# AirSensor.net
KiCad netlist of a schematic drawn in EAGLE
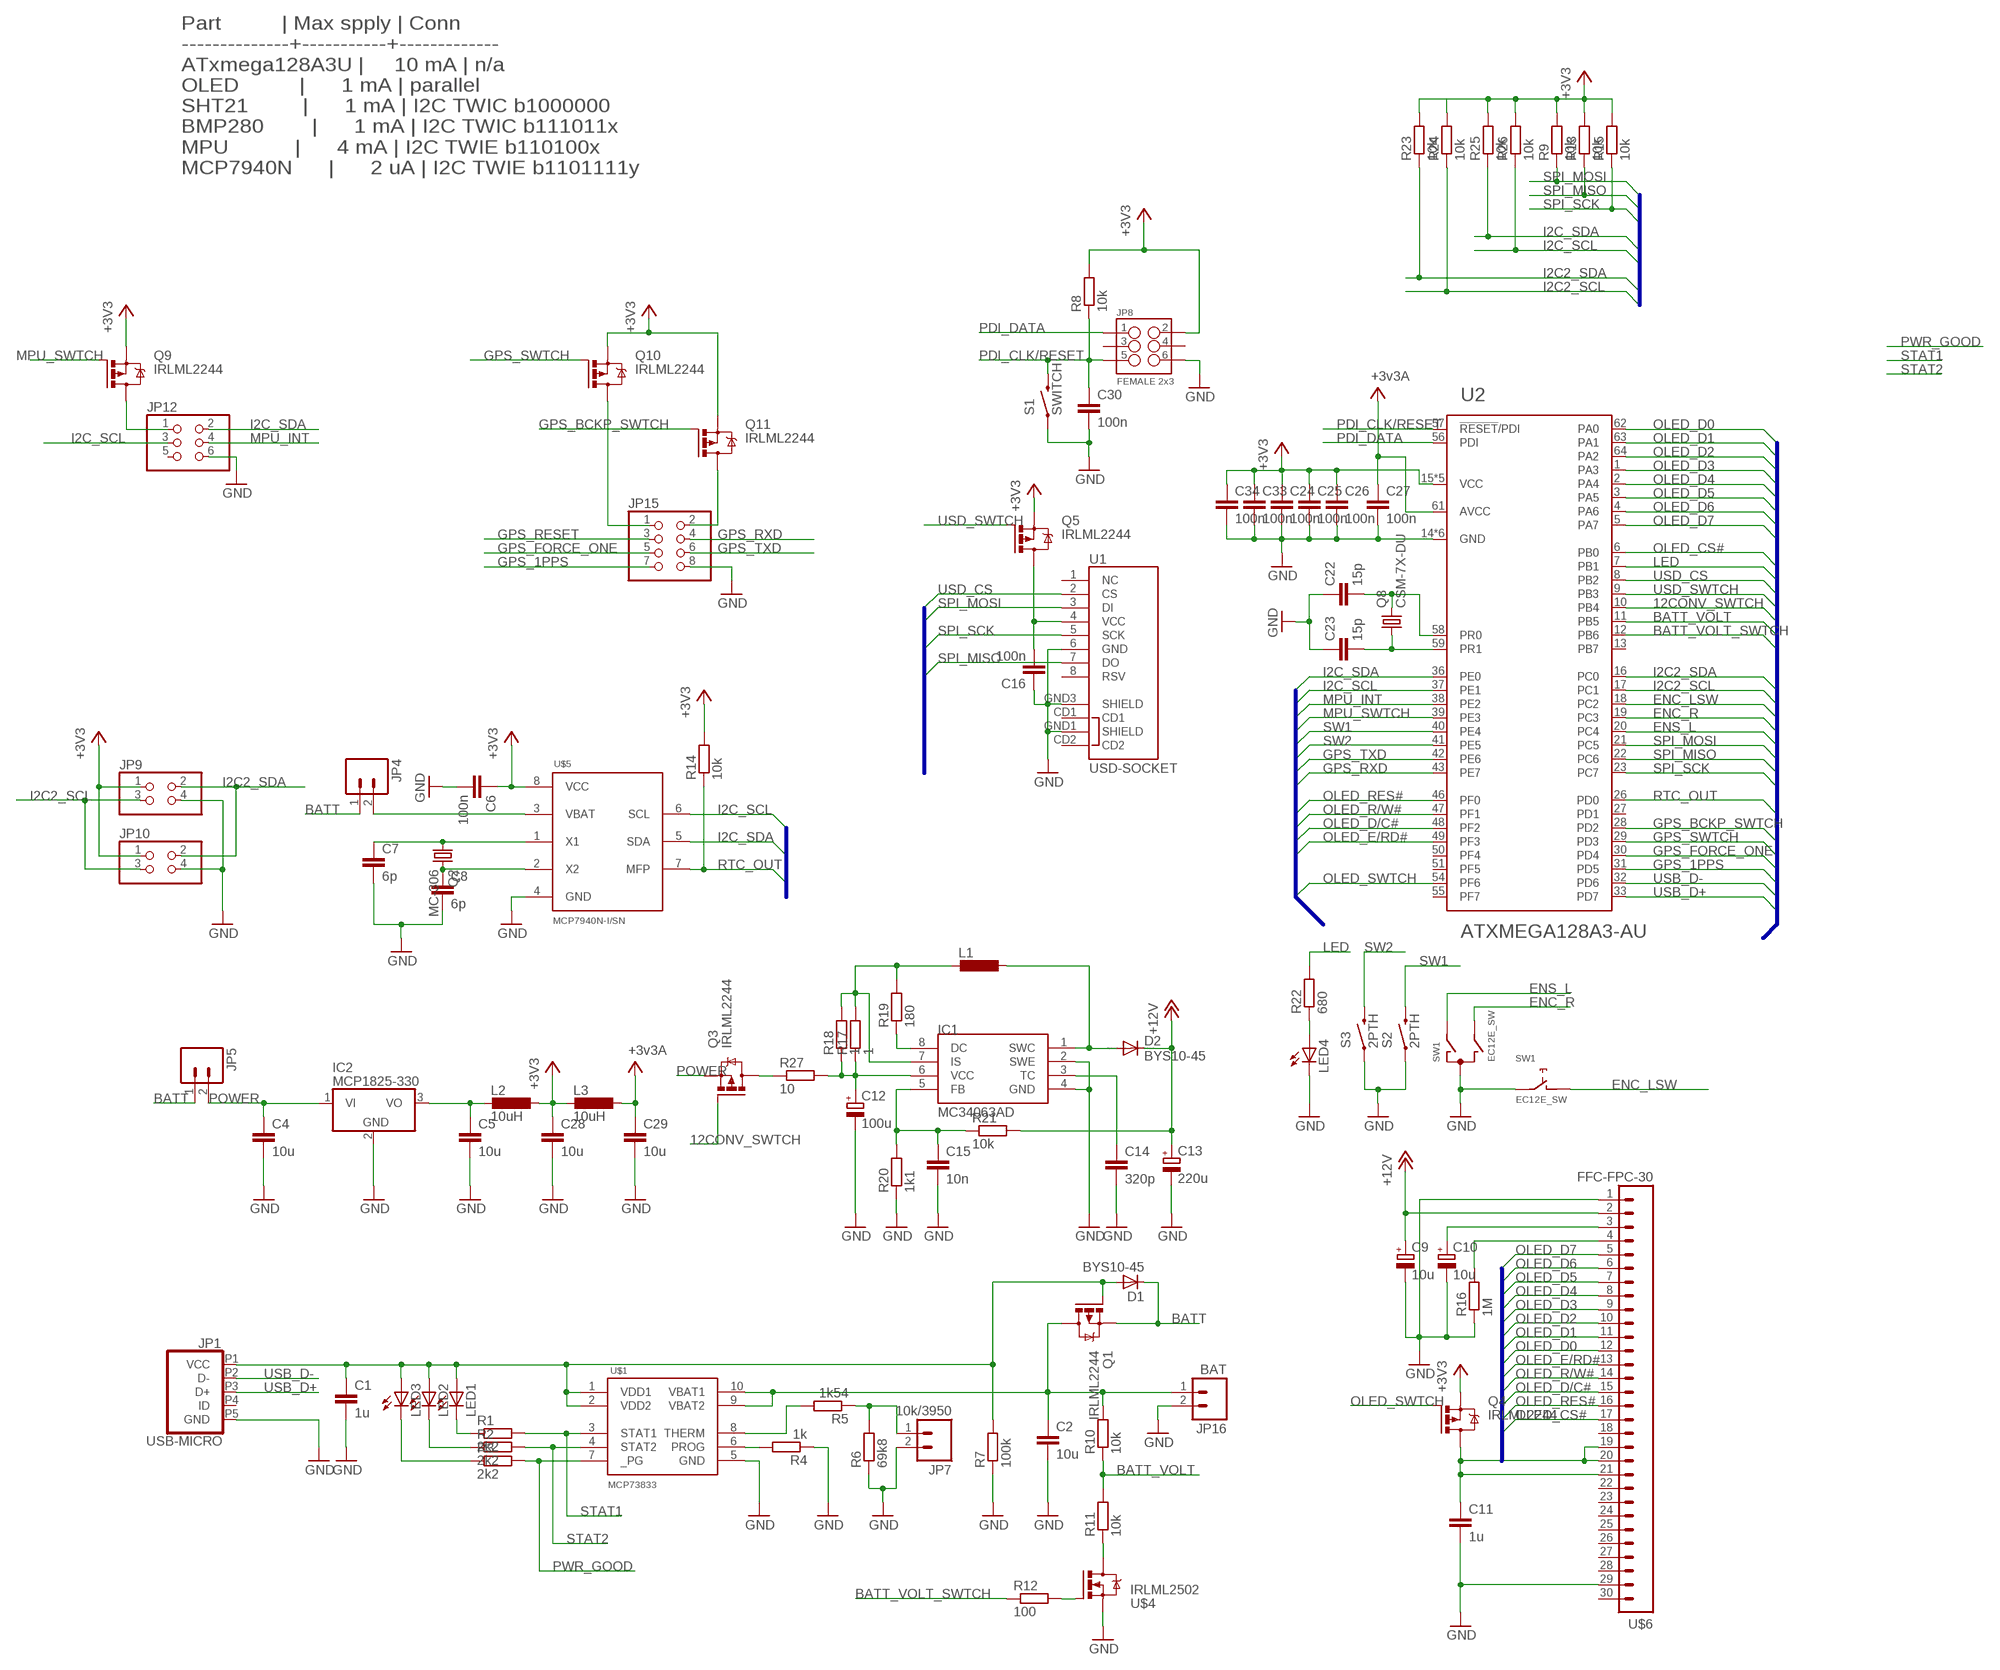
[diagram p0: schematic, sheet 1]

(export (version "E")
  (design (tool "Eeschema 10.0.6"))
  (components
    (comp (ref "C1")
      (value "1u")
      (footprint "eagle-import:C1206")
      (libsource (lib "eagle-import") (part "C-EUC1206"))
    )
    (comp (ref "C2")
      (value "10u")
      (footprint "eagle-import:C0805")
      (libsource (lib "eagle-import") (part "C-EUC0805"))
    )
    (comp (ref "C4")
      (value "10u")
      (footprint "eagle-import:C0805")
      (libsource (lib "eagle-import") (part "C-EUC0805"))
    )
    (comp (ref "C5")
      (value "10u")
      (footprint "eagle-import:C0805")
      (libsource (lib "eagle-import") (part "C-EUC0805"))
    )
    (comp (ref "C6")
      (value "100n")
      (footprint "eagle-import:C0805")
      (libsource (lib "eagle-import") (part "C-EUC0805"))
    )
    (comp (ref "C7")
      (value "6p")
      (footprint "eagle-import:C0805")
      (libsource (lib "eagle-import") (part "C-EUC0805"))
    )
    (comp (ref "C8")
      (value "6p")
      (footprint "eagle-import:C0805")
      (libsource (lib "eagle-import") (part "C-EUC0805"))
    )
    (comp (ref "C9")
      (value "10u")
      (footprint "eagle-import:UD-4X5,8_NICHICON")
      (libsource (lib "eagle-import") (part "CPOL-EUUD-4X5,8"))
    )
    (comp (ref "C10")
      (value "10u")
      (footprint "eagle-import:UD-4X5,8_NICHICON")
      (libsource (lib "eagle-import") (part "CPOL-EUUD-4X5,8"))
    )
    (comp (ref "C11")
      (value "1u")
      (footprint "eagle-import:C0805")
      (libsource (lib "eagle-import") (part "C-EUC0805"))
    )
    (comp (ref "C12")
      (value "100u")
      (footprint "eagle-import:SANYO-OSCON_SMD_C6")
      (libsource (lib "eagle-import") (part "CPOL-EUSANYO_SMD_C6"))
    )
    (comp (ref "C13")
      (value "220u")
      (footprint "eagle-import:SANYO-OSCON_SMD_C6")
      (libsource (lib "eagle-import") (part "CPOL-EUSANYO_SMD_C6"))
    )
    (comp (ref "C14")
      (value "320p")
      (footprint "eagle-import:C0805")
      (libsource (lib "eagle-import") (part "C-EUC0805"))
    )
    (comp (ref "C15")
      (value "10n")
      (footprint "eagle-import:C0805")
      (libsource (lib "eagle-import") (part "C-EUC0805"))
    )
    (comp (ref "C16")
      (value "100n")
      (footprint "eagle-import:C0805")
      (libsource (lib "eagle-import") (part "C-EUC0805"))
    )
    (comp (ref "C22")
      (value "15p")
      (footprint "eagle-import:C0805")
      (libsource (lib "eagle-import") (part "C-EUC0805"))
    )
    (comp (ref "C23")
      (value "15p")
      (footprint "eagle-import:C0805")
      (libsource (lib "eagle-import") (part "C-EUC0805"))
    )
    (comp (ref "C24")
      (value "100n")
      (footprint "eagle-import:C0805")
      (libsource (lib "eagle-import") (part "C-EUC0805"))
    )
    (comp (ref "C25")
      (value "100n")
      (footprint "eagle-import:C0805")
      (libsource (lib "eagle-import") (part "C-EUC0805"))
    )
    (comp (ref "C26")
      (value "100n")
      (footprint "eagle-import:C0805")
      (libsource (lib "eagle-import") (part "C-EUC0805"))
    )
    (comp (ref "C27")
      (value "100n")
      (footprint "eagle-import:C0805")
      (libsource (lib "eagle-import") (part "C-EUC0805"))
    )
    (comp (ref "C28")
      (value "10u")
      (footprint "eagle-import:C0805")
      (libsource (lib "eagle-import") (part "C-EUC0805"))
    )
    (comp (ref "C29")
      (value "10u")
      (footprint "eagle-import:C0805")
      (libsource (lib "eagle-import") (part "C-EUC0805"))
    )
    (comp (ref "C30")
      (value "100n")
      (footprint "eagle-import:C0805")
      (libsource (lib "eagle-import") (part "C-EUC0805"))
    )
    (comp (ref "C33")
      (value "100n")
      (footprint "eagle-import:C0805")
      (libsource (lib "eagle-import") (part "C-EUC0805"))
    )
    (comp (ref "C34")
      (value "100n")
      (footprint "eagle-import:C0805")
      (libsource (lib "eagle-import") (part "C-EUC0805"))
    )
    (comp (ref "D1")
      (value "BYS10-45")
      (footprint "eagle-import:SOD106A")
      (fields (field (name "MPN") "BYS10/45"))
      (libsource (lib "eagle-import") (part "BYS10"))
    )
    (comp (ref "D2")
      (value "BYS10-45")
      (footprint "eagle-import:SOD123")
      (libsource (lib "eagle-import") (part "MBR0520LT"))
    )
    (comp (ref "IC1")
      (value "MC34063AD")
      (footprint "eagle-import:SOIC8")
      (libsource (lib "eagle-import") (part "MC34063AD"))
    )
    (comp (ref "IC2")
      (value "MCP1825-330")
      (footprint "eagle-import:SOT223")
      (libsource (lib "eagle-import") (part "MCP1703DB"))
    )
    (comp (ref "JP1")
      (value "USB-MICRO")
      (footprint "eagle-import:HIROSE-ZX62-AB-5PA(11)")
      (libsource (lib "eagle-import") (part "USB-MICRO"))
    )
    (comp (ref "JP4")
      (value "M02PTH")
      (footprint "eagle-import:1X02")
      (libsource (lib "eagle-import") (part "M02PTH"))
    )
    (comp (ref "JP5")
      (value "M02PTH")
      (footprint "eagle-import:1X02")
      (libsource (lib "eagle-import") (part "M02PTH"))
    )
    (comp (ref "JP7")
      (value "10k/3950")
      (footprint "eagle-import:1X02")
      (libsource (lib "eagle-import") (part "M02PTH"))
    )
    (comp (ref "JP8")
      (value "FEMALE 2x3")
      (footprint "eagle-import:2X3")
      (libsource (lib "eagle-import") (part "M03X2FEMALE"))
    )
    (comp (ref "JP9")
      (value "PINHD-2X2/90-SOCKET")
      (footprint "eagle-import:2X02S_90")
      (libsource (lib "eagle-import") (part "PINHD-2X2/90-SOCKET"))
    )
    (comp (ref "JP10")
      (value "PINHD-2X2/90-SOCKET")
      (footprint "eagle-import:2X02S_90")
      (libsource (lib "eagle-import") (part "PINHD-2X2/90-SOCKET"))
    )
    (comp (ref "JP12")
      (value "PINHD-2X3/90-SOCKET")
      (footprint "eagle-import:2X03S_90")
      (libsource (lib "eagle-import") (part "PINHD-2X3/90-SOCKET"))
    )
    (comp (ref "JP15")
      (value "PINHD-2X4/90-SOCKET")
      (footprint "eagle-import:2X04S_90")
      (libsource (lib "eagle-import") (part "PINHD-2X4/90-SOCKET"))
    )
    (comp (ref "JP16")
      (value "BAT")
      (footprint "eagle-import:1X02")
      (libsource (lib "eagle-import") (part "M02PTH"))
    )
    (comp (ref "L1")
      (value "L-EUTFI0307")
      (footprint "eagle-import:TFI0307")
      (libsource (lib "eagle-import") (part "L-EUTFI0307"))
    )
    (comp (ref "L2")
      (value "10uH")
      (footprint "eagle-import:L3225P")
      (libsource (lib "eagle-import") (part "L-EUL3225P"))
    )
    (comp (ref "L3")
      (value "10uH")
      (footprint "eagle-import:L3225P")
      (libsource (lib "eagle-import") (part "L-EUL3225P"))
    )
    (comp (ref "LED1")
      (value "LEDCHIPLED_1206")
      (footprint "eagle-import:CHIPLED_1206")
      (libsource (lib "eagle-import") (part "LEDCHIPLED_1206"))
    )
    (comp (ref "LED2")
      (value "LEDCHIPLED_1206")
      (footprint "eagle-import:CHIPLED_1206")
      (libsource (lib "eagle-import") (part "LEDCHIPLED_1206"))
    )
    (comp (ref "LED3")
      (value "LEDCHIPLED_1206")
      (footprint "eagle-import:CHIPLED_1206")
      (libsource (lib "eagle-import") (part "LEDCHIPLED_1206"))
    )
    (comp (ref "LED4")
      (value "LEDSML1206")
      (footprint "eagle-import:SML1206")
      (libsource (lib "eagle-import") (part "LEDSML1206"))
    )
    (comp (ref "Q1")
      (value "IRLML2244")
      (footprint "eagle-import:MICRO3")
      (libsource (lib "eagle-import") (part "IRLML5203"))
    )
    (comp (ref "Q2")
      (value "MC-306")
      (footprint "eagle-import:MC-306")
      (fields (field (name "MPN") "MC-306 60.0KHZ  100PPM ,12.5PF"))
      (libsource (lib "eagle-import") (part "MC-306"))
    )
    (comp (ref "Q3")
      (value "IRLML2244")
      (footprint "eagle-import:MICRO3")
      (libsource (lib "eagle-import") (part "IRLML5203"))
    )
    (comp (ref "Q4")
      (value "IRLML2244")
      (footprint "eagle-import:MICRO3")
      (libsource (lib "eagle-import") (part "IRLML5203"))
    )
    (comp (ref "Q5")
      (value "IRLML2244")
      (footprint "eagle-import:MICRO3")
      (libsource (lib "eagle-import") (part "IRLML5203"))
    )
    (comp (ref "Q8")
      (value "CSM-7X-DU")
      (footprint "eagle-import:CSM-7X-DU")
      (libsource (lib "eagle-import") (part "CSM-7X-DU"))
    )
    (comp (ref "Q9")
      (value "IRLML2244")
      (footprint "eagle-import:MICRO3")
      (libsource (lib "eagle-import") (part "IRLML5203"))
    )
    (comp (ref "Q10")
      (value "IRLML2244")
      (footprint "eagle-import:MICRO3")
      (libsource (lib "eagle-import") (part "IRLML5203"))
    )
    (comp (ref "Q11")
      (value "IRLML2244")
      (footprint "eagle-import:MICRO3")
      (libsource (lib "eagle-import") (part "IRLML5203"))
    )
    (comp (ref "R1")
      (value "2k2")
      (footprint "eagle-import:R0805")
      (libsource (lib "eagle-import") (part "R-EU_R0805"))
    )
    (comp (ref "R2")
      (value "2k2")
      (footprint "eagle-import:R0805")
      (libsource (lib "eagle-import") (part "R-EU_R0805"))
    )
    (comp (ref "R3")
      (value "2k2")
      (footprint "eagle-import:R0805")
      (libsource (lib "eagle-import") (part "R-EU_R0805"))
    )
    (comp (ref "R4")
      (value "1k")
      (footprint "eagle-import:R0805")
      (libsource (lib "eagle-import") (part "R-EU_R0805"))
    )
    (comp (ref "R5")
      (value "1k54")
      (footprint "eagle-import:R0805")
      (libsource (lib "eagle-import") (part "R-EU_R0805"))
    )
    (comp (ref "R6")
      (value "69k8")
      (footprint "eagle-import:R0805")
      (libsource (lib "eagle-import") (part "R-EU_R0805"))
    )
    (comp (ref "R7")
      (value "100k")
      (footprint "eagle-import:R0805")
      (libsource (lib "eagle-import") (part "R-EU_R0805"))
    )
    (comp (ref "R8")
      (value "10k")
      (footprint "eagle-import:R0805")
      (libsource (lib "eagle-import") (part "R-EU_R0805"))
    )
    (comp (ref "R9")
      (value "10k")
      (footprint "eagle-import:R0805")
      (libsource (lib "eagle-import") (part "R-EU_R0805"))
    )
    (comp (ref "R10")
      (value "10k")
      (footprint "eagle-import:R0805")
      (libsource (lib "eagle-import") (part "R-EU_R0805"))
    )
    (comp (ref "R11")
      (value "10k")
      (footprint "eagle-import:R0805")
      (libsource (lib "eagle-import") (part "R-EU_R0805"))
    )
    (comp (ref "R12")
      (value "100")
      (footprint "eagle-import:R0805")
      (libsource (lib "eagle-import") (part "R-EU_R0805"))
    )
    (comp (ref "R13")
      (value "10k")
      (footprint "eagle-import:R0805")
      (libsource (lib "eagle-import") (part "R-EU_R0805"))
    )
    (comp (ref "R14")
      (value "10k")
      (footprint "eagle-import:R0805")
      (libsource (lib "eagle-import") (part "R-EU_R0805"))
    )
    (comp (ref "R15")
      (value "10k")
      (footprint "eagle-import:R0805")
      (libsource (lib "eagle-import") (part "R-EU_R0805"))
    )
    (comp (ref "R16")
      (value "1M")
      (footprint "eagle-import:R1206")
      (libsource (lib "eagle-import") (part "R-EU_R1206"))
    )
    (comp (ref "R17")
      (value "1")
      (footprint "eagle-import:R0805")
      (libsource (lib "eagle-import") (part "R-EU_R0805"))
    )
    (comp (ref "R18")
      (value "1")
      (footprint "eagle-import:R0805")
      (libsource (lib "eagle-import") (part "R-EU_R0805"))
    )
    (comp (ref "R19")
      (value "180")
      (footprint "eagle-import:R0805")
      (libsource (lib "eagle-import") (part "R-EU_R0805"))
    )
    (comp (ref "R20")
      (value "1k1")
      (footprint "eagle-import:R0805")
      (libsource (lib "eagle-import") (part "R-EU_R0805"))
    )
    (comp (ref "R21")
      (value "10k")
      (footprint "eagle-import:R0805")
      (libsource (lib "eagle-import") (part "R-EU_R0805"))
    )
    (comp (ref "R22")
      (value "680")
      (footprint "eagle-import:R0805")
      (libsource (lib "eagle-import") (part "R-EU_R0805"))
    )
    (comp (ref "R23")
      (value "10k")
      (footprint "eagle-import:R0805")
      (libsource (lib "eagle-import") (part "R-EU_R0805"))
    )
    (comp (ref "R24")
      (value "10k")
      (footprint "eagle-import:R0805")
      (libsource (lib "eagle-import") (part "R-EU_R0805"))
    )
    (comp (ref "R25")
      (value "10k")
      (footprint "eagle-import:R0805")
      (libsource (lib "eagle-import") (part "R-EU_R0805"))
    )
    (comp (ref "R26")
      (value "10k")
      (footprint "eagle-import:R0805")
      (libsource (lib "eagle-import") (part "R-EU_R0805"))
    )
    (comp (ref "R27")
      (value "10")
      (footprint "eagle-import:R1206")
      (libsource (lib "eagle-import") (part "R-EU_R1206"))
    )
    (comp (ref "S1")
      (value "SWITCH")
      (footprint "eagle-import:TACTILE-PTH-SIDEEZ")
      (libsource (lib "eagle-import") (part "SWITCH-MOMENTARY-2SIDE_EZ"))
    )
    (comp (ref "S2")
      (value "2PTH")
      (footprint "eagle-import:TACTILE_SWITCH_TALL")
      (libsource (lib "eagle-import") (part "SWITCH-MOMENTARY-2SMD-4"))
    )
    (comp (ref "S3")
      (value "2PTH")
      (footprint "eagle-import:TACTILE_SWITCH_TALL")
      (libsource (lib "eagle-import") (part "SWITCH-MOMENTARY-2SMD-4"))
    )
    (comp (ref "SW1")
      (value "EC12E_SW")
      (footprint "eagle-import:ALPS_EC12E_SW")
      (fields (field (name "MPN") "EC12E2424407"))
      (libsource (lib "eagle-import") (part "EC12E_SW"))
    )
    (comp (ref "U$1")
      (value "MCP73833")
      (footprint "eagle-import:MSOP10")
      (libsource (lib "eagle-import") (part "MCP73833"))
    )
    (comp (ref "U$4")
      (value "IRLML2502")
      (footprint "eagle-import:MICRO3")
      (libsource (lib "eagle-import") (part "IRLML2502"))
    )
    (comp (ref "U$5")
      (value "MCP7940N-I/SN")
      (footprint "eagle-import:SOIC8")
      (libsource (lib "eagle-import") (part "MCP7940N-I/SN"))
    )
    (comp (ref "U$6")
      (value "FFC-FPC-30")
      (footprint "eagle-import:FFC-FPC-30V")
      (libsource (lib "eagle-import") (part "FFC-FPC-30"))
    )
    (comp (ref "U1")
      (value "USD-SOCKET")
      (footprint "eagle-import:MICROSD_1_1")
      (libsource (lib "eagle-import") (part "USD-SOCKET"))
    )
    (comp (ref "U2")
      (value "ATXMEGA128A3-AU")
      (footprint "eagle-import:TQFP-64A-64")
      (libsource (lib "eagle-import") (part "ATXMEGA128A3-AU"))
    )
  )
  (nets
    (net (code "1") (name "+3V3") (class "Default")
      (node (ref "C24") (pin "1") (pinfunction "1_1") (pintype "passive"))
      (node (ref "C25") (pin "1") (pinfunction "1_1") (pintype "passive"))
      (node (ref "C26") (pin "1") (pinfunction "1_1") (pintype "passive"))
      (node (ref "C28") (pin "1") (pinfunction "1_1") (pintype "passive"))
      (node (ref "C33") (pin "1") (pinfunction "1_1") (pintype "passive"))
      (node (ref "C34") (pin "1") (pinfunction "1_1") (pintype "passive"))
      (node (ref "C6") (pin "1") (pinfunction "1_1") (pintype "passive"))
      (node (ref "JP10") (pin "1") (pinfunction "1_1") (pintype "passive"))
      (node (ref "JP8") (pin "2") (pinfunction "2_2") (pintype "bidirectional"))
      (node (ref "JP9") (pin "1") (pinfunction "1_1") (pintype "passive"))
      (node (ref "L2") (pin "1") (pinfunction "1_1") (pintype "passive"))
      (node (ref "L3") (pin "2") (pinfunction "2_2") (pintype "passive"))
      (node (ref "Q10") (pin "2") (pinfunction "S_2") (pintype "passive"))
      (node (ref "Q11") (pin "2") (pinfunction "S_2") (pintype "passive"))
      (node (ref "Q4") (pin "2") (pinfunction "S_2") (pintype "passive"))
      (node (ref "Q5") (pin "2") (pinfunction "S_2") (pintype "passive"))
      (node (ref "Q9") (pin "2") (pinfunction "S_2") (pintype "passive"))
      (node (ref "R13") (pin "2") (pinfunction "2_2") (pintype "passive"))
      (node (ref "R14") (pin "2") (pinfunction "2_2") (pintype "passive"))
      (node (ref "R15") (pin "2") (pinfunction "2_2") (pintype "passive"))
      (node (ref "R23") (pin "2") (pinfunction "2_2") (pintype "passive"))
      (node (ref "R24") (pin "2") (pinfunction "2_2") (pintype "passive"))
      (node (ref "R25") (pin "2") (pinfunction "2_2") (pintype "passive"))
      (node (ref "R26") (pin "2") (pinfunction "2_2") (pintype "passive"))
      (node (ref "R8") (pin "2") (pinfunction "2_2") (pintype "passive"))
      (node (ref "R9") (pin "2") (pinfunction "2_2") (pintype "passive"))
      (node (ref "U$5") (pin "8") (pinfunction "VCC_8") (pintype "power_in"))
      (node (ref "U2") (pin "15") (pinfunction "VCC_15") (pintype "power_in"))
      (node (ref "U2") (pin "25") (pinfunction "VCC_25") (pintype "power_in"))
      (node (ref "U2") (pin "35") (pinfunction "VCC_35") (pintype "power_in"))
      (node (ref "U2") (pin "45") (pinfunction "VCC_45") (pintype "power_in"))
      (node (ref "U2") (pin "53") (pinfunction "VCC_53") (pintype "power_in"))
    )
    (net (code "2") (name "+3v3A") (class "Default")
      (node (ref "C27") (pin "1") (pinfunction "1_1") (pintype "passive"))
      (node (ref "C29") (pin "1") (pinfunction "1_1") (pintype "passive"))
      (node (ref "L3") (pin "1") (pinfunction "1_1") (pintype "passive"))
      (node (ref "U2") (pin "61") (pinfunction "AVCC_61") (pintype "power_in"))
    )
    (net (code "3") (name "+12V") (class "Default")
      (node (ref "C13") (pin "+") (pinfunction "+_+") (pintype "passive"))
      (node (ref "C9") (pin "+") (pinfunction "+_+") (pintype "passive"))
      (node (ref "D2") (pin "C") (pinfunction "C_C") (pintype "passive"))
      (node (ref "R21") (pin "2") (pinfunction "2_2") (pintype "passive"))
      (node (ref "U$6") (pin "2") (pinfunction "2_2") (pintype "passive"))
    )
    (net (code "4") (name "/12CONV_SWTCH") (class "Default")
      (node (ref "Q3") (pin "1") (pinfunction "G_1") (pintype "passive"))
      (node (ref "U2") (pin "10") (pinfunction "PB4_10") (pintype "bidirectional"))
    )
    (net (code "5") (name "/BATT") (class "Default")
      (node (ref "D1") (pin "K") (pinfunction "K_K") (pintype "passive"))
      (node (ref "JP4") (pin "1") (pinfunction "1_1") (pintype "passive"))
      (node (ref "JP5") (pin "1") (pinfunction "1_1") (pintype "passive"))
      (node (ref "Q1") (pin "2") (pinfunction "S_2") (pintype "passive"))
    )
    (net (code "6") (name "/BATT_VOLT") (class "Default")
      (node (ref "R10") (pin "1") (pinfunction "1_1") (pintype "passive"))
      (node (ref "R11") (pin "2") (pinfunction "2_2") (pintype "passive"))
      (node (ref "U2") (pin "11") (pinfunction "PB5_11") (pintype "bidirectional"))
    )
    (net (code "7") (name "/BATT_VOLT_SWTCH") (class "Default")
      (node (ref "R12") (pin "1") (pinfunction "1_1") (pintype "passive"))
      (node (ref "U2") (pin "12") (pinfunction "PB6_12") (pintype "bidirectional"))
    )
    (net (code "8") (name "/ENC_LSW") (class "Default")
      (node (ref "SW1") (pin "D") (pinfunction "1_D") (pintype "passive"))
      (node (ref "U2") (pin "18") (pinfunction "PC2_18") (pintype "bidirectional"))
    )
    (net (code "9") (name "/ENC_R") (class "Default")
      (node (ref "SW1") (pin "B") (pinfunction "B_B") (pintype "passive"))
      (node (ref "U2") (pin "19") (pinfunction "PC3_19") (pintype "bidirectional"))
    )
    (net (code "10") (name "/ENS_L") (class "Default")
      (node (ref "SW1") (pin "A") (pinfunction "A_A") (pintype "passive"))
      (node (ref "U2") (pin "20") (pinfunction "PC4_20") (pintype "bidirectional"))
    )
    (net (code "11") (name "/GPS_1PPS") (class "Default")
      (node (ref "JP15") (pin "7") (pinfunction "7_7") (pintype "passive"))
      (node (ref "U2") (pin "31") (pinfunction "PD5_31") (pintype "bidirectional"))
    )
    (net (code "12") (name "/GPS_BCKP_SWTCH") (class "Default")
      (node (ref "Q11") (pin "1") (pinfunction "G_1") (pintype "passive"))
      (node (ref "U2") (pin "28") (pinfunction "PD2_28") (pintype "bidirectional"))
    )
    (net (code "13") (name "/GPS_FORCE_ONE") (class "Default")
      (node (ref "JP15") (pin "5") (pinfunction "5_5") (pintype "passive"))
      (node (ref "U2") (pin "30") (pinfunction "PD4_30") (pintype "bidirectional"))
    )
    (net (code "14") (name "/GPS_RESET") (class "Default")
      (node (ref "JP15") (pin "3") (pinfunction "3_3") (pintype "passive"))
    )
    (net (code "15") (name "/GPS_RXD") (class "Default")
      (node (ref "JP15") (pin "4") (pinfunction "4_4") (pintype "passive"))
      (node (ref "U2") (pin "43") (pinfunction "PE7_43") (pintype "bidirectional"))
    )
    (net (code "16") (name "/GPS_SWTCH") (class "Default")
      (node (ref "Q10") (pin "1") (pinfunction "G_1") (pintype "passive"))
      (node (ref "U2") (pin "29") (pinfunction "PD3_29") (pintype "bidirectional"))
    )
    (net (code "17") (name "/GPS_TXD") (class "Default")
      (node (ref "JP15") (pin "6") (pinfunction "6_6") (pintype "passive"))
      (node (ref "U2") (pin "42") (pinfunction "PE6_42") (pintype "bidirectional"))
    )
    (net (code "18") (name "/I2C2_SCL") (class "Default")
      (node (ref "JP10") (pin "3") (pinfunction "3_3") (pintype "passive"))
      (node (ref "JP9") (pin "3") (pinfunction "3_3") (pintype "passive"))
      (node (ref "R24") (pin "1") (pinfunction "1_1") (pintype "passive"))
      (node (ref "U2") (pin "17") (pinfunction "PC1_17") (pintype "bidirectional"))
    )
    (net (code "19") (name "/I2C2_SDA") (class "Default")
      (node (ref "JP10") (pin "2") (pinfunction "2_2") (pintype "passive"))
      (node (ref "JP9") (pin "2") (pinfunction "2_2") (pintype "passive"))
      (node (ref "R23") (pin "1") (pinfunction "1_1") (pintype "passive"))
      (node (ref "U2") (pin "16") (pinfunction "PC0_16") (pintype "bidirectional"))
    )
    (net (code "20") (name "/I2C_SCL") (class "Default")
      (node (ref "JP12") (pin "3") (pinfunction "3_3") (pintype "passive"))
      (node (ref "R26") (pin "1") (pinfunction "1_1") (pintype "passive"))
      (node (ref "U$5") (pin "6") (pinfunction "SCL_6") (pintype "bidirectional"))
      (node (ref "U2") (pin "37") (pinfunction "PE1_37") (pintype "bidirectional"))
    )
    (net (code "21") (name "/I2C_SDA") (class "Default")
      (node (ref "JP12") (pin "2") (pinfunction "2_2") (pintype "passive"))
      (node (ref "R25") (pin "1") (pinfunction "1_1") (pintype "passive"))
      (node (ref "U$5") (pin "5") (pinfunction "SDA_5") (pintype "bidirectional"))
      (node (ref "U2") (pin "36") (pinfunction "PE0_36") (pintype "bidirectional"))
    )
    (net (code "22") (name "/LED") (class "Default")
      (node (ref "R22") (pin "2") (pinfunction "2_2") (pintype "passive"))
      (node (ref "U2") (pin "7") (pinfunction "PB1_7") (pintype "bidirectional"))
    )
    (net (code "23") (name "/MPU_INT") (class "Default")
      (node (ref "JP12") (pin "4") (pinfunction "4_4") (pintype "passive"))
      (node (ref "U2") (pin "38") (pinfunction "PE2_38") (pintype "bidirectional"))
    )
    (net (code "24") (name "/MPU_SWTCH") (class "Default")
      (node (ref "Q9") (pin "1") (pinfunction "G_1") (pintype "passive"))
      (node (ref "U2") (pin "39") (pinfunction "PE3_39") (pintype "bidirectional"))
    )
    (net (code "25") (name "/OLED_CS#") (class "Default")
      (node (ref "U$6") (pin "17") (pinfunction "17_17") (pintype "passive"))
      (node (ref "U2") (pin "6") (pinfunction "PB0_6") (pintype "bidirectional"))
    )
    (net (code "26") (name "/OLED_D0") (class "Default")
      (node (ref "U$6") (pin "12") (pinfunction "12_12") (pintype "passive"))
      (node (ref "U2") (pin "62") (pinfunction "PA0_62") (pintype "bidirectional"))
    )
    (net (code "27") (name "/OLED_D1") (class "Default")
      (node (ref "U$6") (pin "11") (pinfunction "11_11") (pintype "passive"))
      (node (ref "U2") (pin "63") (pinfunction "PA1_63") (pintype "bidirectional"))
    )
    (net (code "28") (name "/OLED_D2") (class "Default")
      (node (ref "U$6") (pin "10") (pinfunction "10_10") (pintype "passive"))
      (node (ref "U2") (pin "64") (pinfunction "PA2_64") (pintype "bidirectional"))
    )
    (net (code "29") (name "/OLED_D3") (class "Default")
      (node (ref "U$6") (pin "9") (pinfunction "9_9") (pintype "passive"))
      (node (ref "U2") (pin "1") (pinfunction "PA3_1") (pintype "bidirectional"))
    )
    (net (code "30") (name "/OLED_D4") (class "Default")
      (node (ref "U$6") (pin "8") (pinfunction "8_8") (pintype "passive"))
      (node (ref "U2") (pin "2") (pinfunction "PA4_2") (pintype "bidirectional"))
    )
    (net (code "31") (name "/OLED_D5") (class "Default")
      (node (ref "U$6") (pin "7") (pinfunction "7_7") (pintype "passive"))
      (node (ref "U2") (pin "3") (pinfunction "PA5_3") (pintype "bidirectional"))
    )
    (net (code "32") (name "/OLED_D6") (class "Default")
      (node (ref "U$6") (pin "6") (pinfunction "6_6") (pintype "passive"))
      (node (ref "U2") (pin "4") (pinfunction "PA6_4") (pintype "bidirectional"))
    )
    (net (code "33") (name "/OLED_D7") (class "Default")
      (node (ref "U$6") (pin "5") (pinfunction "5_5") (pintype "passive"))
      (node (ref "U2") (pin "5") (pinfunction "PA7_5") (pintype "bidirectional"))
    )
    (net (code "34") (name "/OLED_D{slash}C#") (class "Default")
      (node (ref "U$6") (pin "15") (pinfunction "15_15") (pintype "passive"))
      (node (ref "U2") (pin "48") (pinfunction "PF2_48") (pintype "bidirectional"))
    )
    (net (code "35") (name "/OLED_E{slash}RD#") (class "Default")
      (node (ref "U$6") (pin "13") (pinfunction "13_13") (pintype "passive"))
      (node (ref "U2") (pin "49") (pinfunction "PF3_49") (pintype "bidirectional"))
    )
    (net (code "36") (name "/OLED_RES#") (class "Default")
      (node (ref "U$6") (pin "16") (pinfunction "16_16") (pintype "passive"))
      (node (ref "U2") (pin "46") (pinfunction "PF0_46") (pintype "bidirectional"))
    )
    (net (code "37") (name "/OLED_R{slash}W#") (class "Default")
      (node (ref "U$6") (pin "14") (pinfunction "14_14") (pintype "passive"))
      (node (ref "U2") (pin "47") (pinfunction "PF1_47") (pintype "bidirectional"))
    )
    (net (code "38") (name "/OLED_SWTCH") (class "Default")
      (node (ref "Q4") (pin "1") (pinfunction "G_1") (pintype "passive"))
      (node (ref "U2") (pin "54") (pinfunction "PF6_54") (pintype "bidirectional"))
    )
    (net (code "39") (name "/PDI_CLK{slash}RESET") (class "Default")
      (node (ref "C30") (pin "1") (pinfunction "1_1") (pintype "passive"))
      (node (ref "JP8") (pin "5") (pinfunction "5_5") (pintype "bidirectional"))
      (node (ref "R8") (pin "1") (pinfunction "1_1") (pintype "passive"))
      (node (ref "S1") (pin "2") (pinfunction "2_2") (pintype "passive"))
      (node (ref "U2") (pin "57") (pinfunction "~{RESET}/PDI_57") (pintype "bidirectional"))
    )
    (net (code "40") (name "/PDI_DATA") (class "Default")
      (node (ref "JP8") (pin "1") (pinfunction "1_1") (pintype "bidirectional"))
      (node (ref "U2") (pin "56") (pinfunction "PDI_56") (pintype "bidirectional"))
    )
    (net (code "41") (name "/POWER") (class "Default")
      (node (ref "C4") (pin "1") (pinfunction "1_1") (pintype "passive"))
      (node (ref "IC2") (pin "1") (pinfunction "VI_1") (pintype "input"))
      (node (ref "JP5") (pin "2") (pinfunction "2_2") (pintype "passive"))
      (node (ref "Q3") (pin "2") (pinfunction "S_2") (pintype "passive"))
    )
    (net (code "42") (name "/PWR_GOOD") (class "Default")
      (node (ref "R3") (pin "2") (pinfunction "2_2") (pintype "passive"))
      (node (ref "U$1") (pin "7") (pinfunction "_PG_7") (pintype "bidirectional"))
    )
    (net (code "43") (name "/RTC_OUT") (class "Default")
      (node (ref "R14") (pin "1") (pinfunction "1_1") (pintype "passive"))
      (node (ref "U$5") (pin "7") (pinfunction "MFP_7") (pintype "output"))
      (node (ref "U2") (pin "26") (pinfunction "PD0_26") (pintype "bidirectional"))
    )
    (net (code "44") (name "/SPI_MISO") (class "Default")
      (node (ref "R13") (pin "1") (pinfunction "1_1") (pintype "passive"))
      (node (ref "U1") (pin "7") (pinfunction "DO_7") (pintype "bidirectional"))
      (node (ref "U2") (pin "22") (pinfunction "PC6_22") (pintype "bidirectional"))
    )
    (net (code "45") (name "/SPI_MOSI") (class "Default")
      (node (ref "R9") (pin "1") (pinfunction "1_1") (pintype "passive"))
      (node (ref "U1") (pin "3") (pinfunction "DI_3") (pintype "bidirectional"))
      (node (ref "U2") (pin "21") (pinfunction "PC5_21") (pintype "bidirectional"))
    )
    (net (code "46") (name "/SPI_SCK") (class "Default")
      (node (ref "R15") (pin "1") (pinfunction "1_1") (pintype "passive"))
      (node (ref "U1") (pin "5") (pinfunction "SCK_5") (pintype "bidirectional"))
      (node (ref "U2") (pin "23") (pinfunction "PC7_23") (pintype "bidirectional"))
    )
    (net (code "47") (name "/STAT1") (class "Default")
      (node (ref "R1") (pin "2") (pinfunction "2_2") (pintype "passive"))
      (node (ref "U$1") (pin "3") (pinfunction "STAT1_3") (pintype "bidirectional"))
    )
    (net (code "48") (name "/STAT2") (class "Default")
      (node (ref "R2") (pin "2") (pinfunction "2_2") (pintype "passive"))
      (node (ref "U$1") (pin "4") (pinfunction "STAT2_4") (pintype "bidirectional"))
    )
    (net (code "49") (name "/SW1") (class "Default")
      (node (ref "S2") (pin "B2") (pinfunction "2_B2") (pintype "passive"))
      (node (ref "U2") (pin "40") (pinfunction "PE4_40") (pintype "bidirectional"))
    )
    (net (code "50") (name "/SW2") (class "Default")
      (node (ref "S3") (pin "B2") (pinfunction "2_B2") (pintype "passive"))
      (node (ref "U2") (pin "41") (pinfunction "PE5_41") (pintype "bidirectional"))
    )
    (net (code "51") (name "/USB_D+") (class "Default")
      (node (ref "JP1") (pin "P3") (pinfunction "D+_P3") (pintype "bidirectional"))
      (node (ref "U2") (pin "33") (pinfunction "PD7_33") (pintype "bidirectional"))
    )
    (net (code "52") (name "/USB_D-") (class "Default")
      (node (ref "JP1") (pin "P2") (pinfunction "D-_P2") (pintype "bidirectional"))
      (node (ref "U2") (pin "32") (pinfunction "PD6_32") (pintype "bidirectional"))
    )
    (net (code "53") (name "/USD_CS") (class "Default")
      (node (ref "U1") (pin "2") (pinfunction "CS_2") (pintype "bidirectional"))
      (node (ref "U2") (pin "8") (pinfunction "PB2_8") (pintype "bidirectional"))
    )
    (net (code "54") (name "/USD_SWTCH") (class "Default")
      (node (ref "Q5") (pin "1") (pinfunction "G_1") (pintype "passive"))
      (node (ref "U2") (pin "9") (pinfunction "PB3_9") (pintype "bidirectional"))
    )
    (net (code "55") (name "GND") (class "Default")
      (node (ref "C1") (pin "2") (pinfunction "2_2") (pintype "passive"))
      (node (ref "C10") (pin "-") (pinfunction "-_-") (pintype "passive"))
      (node (ref "C11") (pin "2") (pinfunction "2_2") (pintype "passive"))
      (node (ref "C12") (pin "-") (pinfunction "-_-") (pintype "passive"))
      (node (ref "C13") (pin "-") (pinfunction "-_-") (pintype "passive"))
      (node (ref "C14") (pin "2") (pinfunction "2_2") (pintype "passive"))
      (node (ref "C15") (pin "2") (pinfunction "2_2") (pintype "passive"))
      (node (ref "C16") (pin "1") (pinfunction "1_1") (pintype "passive"))
      (node (ref "C2") (pin "2") (pinfunction "2_2") (pintype "passive"))
      (node (ref "C22") (pin "1") (pinfunction "1_1") (pintype "passive"))
      (node (ref "C23") (pin "1") (pinfunction "1_1") (pintype "passive"))
      (node (ref "C24") (pin "2") (pinfunction "2_2") (pintype "passive"))
      (node (ref "C25") (pin "2") (pinfunction "2_2") (pintype "passive"))
      (node (ref "C26") (pin "2") (pinfunction "2_2") (pintype "passive"))
      (node (ref "C27") (pin "2") (pinfunction "2_2") (pintype "passive"))
      (node (ref "C28") (pin "2") (pinfunction "2_2") (pintype "passive"))
      (node (ref "C29") (pin "2") (pinfunction "2_2") (pintype "passive"))
      (node (ref "C30") (pin "2") (pinfunction "2_2") (pintype "passive"))
      (node (ref "C33") (pin "2") (pinfunction "2_2") (pintype "passive"))
      (node (ref "C34") (pin "2") (pinfunction "2_2") (pintype "passive"))
      (node (ref "C4") (pin "2") (pinfunction "2_2") (pintype "passive"))
      (node (ref "C5") (pin "2") (pinfunction "2_2") (pintype "passive"))
      (node (ref "C6") (pin "2") (pinfunction "2_2") (pintype "passive"))
      (node (ref "C7") (pin "2") (pinfunction "2_2") (pintype "passive"))
      (node (ref "C8") (pin "2") (pinfunction "2_2") (pintype "passive"))
      (node (ref "C9") (pin "-") (pinfunction "-_-") (pintype "passive"))
      (node (ref "IC1") (pin "2") (pinfunction "SWE_2") (pintype "passive"))
      (node (ref "IC1") (pin "4") (pinfunction "GND_4") (pintype "passive"))
      (node (ref "IC2") (pin "2") (pinfunction "GND_2") (pintype "passive"))
      (node (ref "JP1") (pin "P5") (pinfunction "GND_P5") (pintype "bidirectional"))
      (node (ref "JP10") (pin "4") (pinfunction "4_4") (pintype "passive"))
      (node (ref "JP12") (pin "6") (pinfunction "6_6") (pintype "passive"))
      (node (ref "JP15") (pin "8") (pinfunction "8_8") (pintype "passive"))
      (node (ref "JP16") (pin "2") (pinfunction "2_2") (pintype "passive"))
      (node (ref "JP7") (pin "2") (pinfunction "2_2") (pintype "passive"))
      (node (ref "JP8") (pin "6") (pinfunction "6_6") (pintype "bidirectional"))
      (node (ref "JP9") (pin "4") (pinfunction "4_4") (pintype "passive"))
      (node (ref "LED4") (pin "C") (pinfunction "C_C") (pintype "passive"))
      (node (ref "R16") (pin "1") (pinfunction "1_1") (pintype "passive"))
      (node (ref "R20") (pin "1") (pinfunction "1_1") (pintype "passive"))
      (node (ref "R4") (pin "1") (pinfunction "1_1") (pintype "passive"))
      (node (ref "R6") (pin "1") (pinfunction "1_1") (pintype "passive"))
      (node (ref "R7") (pin "1") (pinfunction "1_1") (pintype "passive"))
      (node (ref "S1") (pin "1") (pinfunction "1_1") (pintype "passive"))
      (node (ref "S2") (pin "A2") (pinfunction "1_A2") (pintype "passive"))
      (node (ref "S3") (pin "A2") (pinfunction "1_A2") (pintype "passive"))
      (node (ref "SW1") (pin "C") (pinfunction "C_C") (pintype "passive"))
      (node (ref "SW1") (pin "E") (pinfunction "2_E") (pintype "passive"))
      (node (ref "U$1") (pin "5") (pinfunction "GND_5") (pintype "bidirectional"))
      (node (ref "U$4") (pin "2") (pinfunction "S_2") (pintype "passive"))
      (node (ref "U$5") (pin "4") (pinfunction "GND_4") (pintype "power_in"))
      (node (ref "U$6") (pin "1") (pinfunction "1_1") (pintype "passive"))
      (node (ref "U$6") (pin "29") (pinfunction "29_29") (pintype "passive"))
      (node (ref "U1") (pin "6") (pinfunction "GND_6") (pintype "bidirectional"))
      (node (ref "U1") (pin "GND1") (pinfunction "SHIELD_GND1") (pintype "bidirectional"))
      (node (ref "U1") (pin "GND3") (pinfunction "SHIELD_GND3") (pintype "bidirectional"))
      (node (ref "U2") (pin "14") (pinfunction "GND_14") (pintype "power_in"))
      (node (ref "U2") (pin "24") (pinfunction "GND_24") (pintype "power_in"))
      (node (ref "U2") (pin "34") (pinfunction "GND_34") (pintype "power_in"))
      (node (ref "U2") (pin "44") (pinfunction "GND_44") (pintype "power_in"))
      (node (ref "U2") (pin "52") (pinfunction "GND_52") (pintype "power_in"))
      (node (ref "U2") (pin "60") (pinfunction "GND_60") (pintype "power_in"))
    )
    (net (code "56") (name "Net-(C10-Pad+)") (class "Default")
      (node (ref "C10") (pin "+") (pinfunction "+_+") (pintype "passive"))
      (node (ref "U$6") (pin "3") (pinfunction "3_3") (pintype "passive"))
    )
    (net (code "57") (name "Net-(IC1-DC)") (class "Default")
      (node (ref "IC1") (pin "8") (pinfunction "DC_8") (pintype "passive"))
      (node (ref "R19") (pin "1") (pinfunction "1_1") (pintype "passive"))
    )
    (net (code "58") (name "Net-(IC1-FB)") (class "Default")
      (node (ref "C15") (pin "1") (pinfunction "1_1") (pintype "passive"))
      (node (ref "IC1") (pin "5") (pinfunction "FB_5") (pintype "passive"))
      (node (ref "R20") (pin "2") (pinfunction "2_2") (pintype "passive"))
      (node (ref "R21") (pin "1") (pinfunction "1_1") (pintype "passive"))
    )
    (net (code "59") (name "Net-(IC1-IS)") (class "Default")
      (node (ref "IC1") (pin "7") (pinfunction "IS_7") (pintype "passive"))
      (node (ref "L1") (pin "2") (pinfunction "2_2") (pintype "passive"))
      (node (ref "R17") (pin "2") (pinfunction "2_2") (pintype "passive"))
      (node (ref "R18") (pin "2") (pinfunction "2_2") (pintype "passive"))
      (node (ref "R19") (pin "2") (pinfunction "2_2") (pintype "passive"))
    )
    (net (code "60") (name "Net-(IC1-SWC)") (class "Default")
      (node (ref "D2") (pin "A") (pinfunction "A_A") (pintype "passive"))
      (node (ref "IC1") (pin "1") (pinfunction "SWC_1") (pintype "passive"))
      (node (ref "L1") (pin "1") (pinfunction "1_1") (pintype "passive"))
    )
    (net (code "61") (name "Net-(IC1-TC)") (class "Default")
      (node (ref "C14") (pin "1") (pinfunction "1_1") (pintype "passive"))
      (node (ref "IC1") (pin "3") (pinfunction "TC_3") (pintype "passive"))
    )
    (net (code "62") (name "Net-(IC1-VCC)") (class "Default")
      (node (ref "C12") (pin "+") (pinfunction "+_+") (pintype "passive"))
      (node (ref "IC1") (pin "6") (pinfunction "VCC_6") (pintype "passive"))
      (node (ref "R17") (pin "1") (pinfunction "1_1") (pintype "passive"))
      (node (ref "R18") (pin "1") (pinfunction "1_1") (pintype "passive"))
      (node (ref "R27") (pin "2") (pinfunction "2_2") (pintype "passive"))
    )
    (net (code "63") (name "Net-(IC2-VO)") (class "Default")
      (node (ref "C5") (pin "1") (pinfunction "1_1") (pintype "passive"))
      (node (ref "IC2") (pin "3") (pinfunction "VO_3") (pintype "passive"))
      (node (ref "L2") (pin "2") (pinfunction "2_2") (pintype "passive"))
    )
    (net (code "64") (name "Net-(JP1-VCC)") (class "Default")
      (node (ref "C1") (pin "1") (pinfunction "1_1") (pintype "passive"))
      (node (ref "D1") (pin "A") (pinfunction "A_A") (pintype "passive"))
      (node (ref "JP1") (pin "P1") (pinfunction "VCC_P1") (pintype "bidirectional"))
      (node (ref "LED1") (pin "A") (pinfunction "A_A") (pintype "passive"))
      (node (ref "LED2") (pin "A") (pinfunction "A_A") (pintype "passive"))
      (node (ref "LED3") (pin "A") (pinfunction "A_A") (pintype "passive"))
      (node (ref "Q1") (pin "1") (pinfunction "G_1") (pintype "passive"))
      (node (ref "R7") (pin "2") (pinfunction "2_2") (pintype "passive"))
      (node (ref "U$1") (pin "1") (pinfunction "VDD1_1") (pintype "bidirectional"))
      (node (ref "U$1") (pin "2") (pinfunction "VDD2_2") (pintype "bidirectional"))
    )
    (net (code "65") (name "Net-(JP7-Pad1)") (class "Default")
      (node (ref "JP7") (pin "1") (pinfunction "1_1") (pintype "passive"))
      (node (ref "R5") (pin "1") (pinfunction "1_1") (pintype "passive"))
      (node (ref "R6") (pin "2") (pinfunction "2_2") (pintype "passive"))
    )
    (net (code "66") (name "Net-(LED1-PadC)") (class "Default")
      (node (ref "LED1") (pin "C") (pinfunction "C_C") (pintype "passive"))
      (node (ref "R1") (pin "1") (pinfunction "1_1") (pintype "passive"))
    )
    (net (code "67") (name "Net-(LED2-PadC)") (class "Default")
      (node (ref "LED2") (pin "C") (pinfunction "C_C") (pintype "passive"))
      (node (ref "R2") (pin "1") (pinfunction "1_1") (pintype "passive"))
    )
    (net (code "68") (name "Net-(LED3-PadC)") (class "Default")
      (node (ref "LED3") (pin "C") (pinfunction "C_C") (pintype "passive"))
      (node (ref "R3") (pin "1") (pinfunction "1_1") (pintype "passive"))
    )
    (net (code "69") (name "Net-(LED4-PadA)") (class "Default")
      (node (ref "LED4") (pin "A") (pinfunction "A_A") (pintype "passive"))
      (node (ref "R22") (pin "1") (pinfunction "1_1") (pintype "passive"))
    )
    (net (code "70") (name "Net-(Q1-D)") (class "Default")
      (node (ref "C2") (pin "1") (pinfunction "1_1") (pintype "passive"))
      (node (ref "JP16") (pin "1") (pinfunction "1_1") (pintype "passive"))
      (node (ref "Q1") (pin "3") (pinfunction "D_3") (pintype "passive"))
      (node (ref "R10") (pin "2") (pinfunction "2_2") (pintype "passive"))
      (node (ref "U$1") (pin "10") (pinfunction "VBAT1_10") (pintype "bidirectional"))
      (node (ref "U$1") (pin "9") (pinfunction "VBAT2_9") (pintype "bidirectional"))
    )
    (net (code "71") (name "Net-(Q2-2)") (class "Default")
      (node (ref "C8") (pin "1") (pinfunction "1_1") (pintype "passive"))
      (node (ref "Q2") (pin "4") (pinfunction "2_4") (pintype "passive"))
      (node (ref "U$5") (pin "2") (pinfunction "X2_2") (pintype "bidirectional"))
    )
    (net (code "72") (name "Net-(Q3-D)") (class "Default")
      (node (ref "Q3") (pin "3") (pinfunction "D_3") (pintype "passive"))
      (node (ref "R27") (pin "1") (pinfunction "1_1") (pintype "passive"))
    )
    (net (code "73") (name "Net-(Q4-D)") (class "Default")
      (node (ref "C11") (pin "1") (pinfunction "1_1") (pintype "passive"))
      (node (ref "Q4") (pin "3") (pinfunction "D_3") (pintype "passive"))
      (node (ref "U$6") (pin "19") (pinfunction "19_19") (pintype "passive"))
      (node (ref "U$6") (pin "20") (pinfunction "20_20") (pintype "passive"))
      (node (ref "U$6") (pin "21") (pinfunction "21_21") (pintype "passive"))
    )
    (net (code "74") (name "Net-(Q5-D)") (class "Default")
      (node (ref "C16") (pin "2") (pinfunction "2_2") (pintype "passive"))
      (node (ref "Q5") (pin "3") (pinfunction "D_3") (pintype "passive"))
      (node (ref "U1") (pin "4") (pinfunction "VCC_4") (pintype "bidirectional"))
    )
    (net (code "75") (name "Net-(Q9-D)") (class "Default")
      (node (ref "JP12") (pin "1") (pinfunction "1_1") (pintype "passive"))
      (node (ref "Q9") (pin "3") (pinfunction "D_3") (pintype "passive"))
    )
    (net (code "76") (name "Net-(Q10-D)") (class "Default")
      (node (ref "JP15") (pin "1") (pinfunction "1_1") (pintype "passive"))
      (node (ref "Q10") (pin "3") (pinfunction "D_3") (pintype "passive"))
    )
    (net (code "77") (name "Net-(Q11-D)") (class "Default")
      (node (ref "JP15") (pin "2") (pinfunction "2_2") (pintype "passive"))
      (node (ref "Q11") (pin "3") (pinfunction "D_3") (pintype "passive"))
    )
    (net (code "78") (name "Net-(R16-Pad2)") (class "Default")
      (node (ref "R16") (pin "2") (pinfunction "2_2") (pintype "passive"))
      (node (ref "U$6") (pin "4") (pinfunction "4_4") (pintype "passive"))
    )
    (net (code "79") (name "Net-(U$1-PROG)") (class "Default")
      (node (ref "R4") (pin "2") (pinfunction "2_2") (pintype "passive"))
      (node (ref "U$1") (pin "6") (pinfunction "PROG_6") (pintype "bidirectional"))
    )
    (net (code "80") (name "Net-(U$1-THERM)") (class "Default")
      (node (ref "R5") (pin "2") (pinfunction "2_2") (pintype "passive"))
      (node (ref "U$1") (pin "8") (pinfunction "THERM_8") (pintype "bidirectional"))
    )
    (net (code "81") (name "Net-(U$4-D)") (class "Default")
      (node (ref "R11") (pin "1") (pinfunction "1_1") (pintype "passive"))
      (node (ref "U$4") (pin "3") (pinfunction "D_3") (pintype "passive"))
    )
    (net (code "82") (name "Net-(U$4-G)") (class "Default")
      (node (ref "R12") (pin "2") (pinfunction "2_2") (pintype "passive"))
      (node (ref "U$4") (pin "1") (pinfunction "G_1") (pintype "passive"))
    )
    (net (code "83") (name "Net-(U$5-VBAT)") (class "Default")
      (node (ref "JP4") (pin "2") (pinfunction "2_2") (pintype "passive"))
      (node (ref "U$5") (pin "3") (pinfunction "VBAT_3") (pintype "power_in"))
    )
    (net (code "84") (name "Net-(U$5-X1)") (class "Default")
      (node (ref "C7") (pin "1") (pinfunction "1_1") (pintype "passive"))
      (node (ref "Q2") (pin "1") (pinfunction "1_1") (pintype "passive"))
      (node (ref "U$5") (pin "1") (pinfunction "X1_1") (pintype "bidirectional"))
    )
    (net (code "85") (name "Net-(U2-PR0)") (class "Default")
      (node (ref "C22") (pin "2") (pinfunction "2_2") (pintype "passive"))
      (node (ref "Q8") (pin "2") (pinfunction "2_2") (pintype "passive"))
      (node (ref "U2") (pin "58") (pinfunction "PR0_58") (pintype "bidirectional"))
    )
    (net (code "86") (name "Net-(U2-PR1)") (class "Default")
      (node (ref "C23") (pin "2") (pinfunction "2_2") (pintype "passive"))
      (node (ref "Q8") (pin "1") (pinfunction "1_1") (pintype "passive"))
      (node (ref "U2") (pin "59") (pinfunction "PR1_59") (pintype "bidirectional"))
    )
    (net (code "87") (name "unconnected-(JP1-ID-PadP4)") (class "Default")
      (node (ref "JP1") (pin "P4") (pinfunction "ID_P4") (pintype "bidirectional"))
    )
    (net (code "88") (name "unconnected-(JP8-Pad3)") (class "Default")
      (node (ref "JP8") (pin "3") (pinfunction "3_3") (pintype "bidirectional"))
    )
    (net (code "89") (name "unconnected-(JP8-Pad4)") (class "Default")
      (node (ref "JP8") (pin "4") (pinfunction "4_4") (pintype "bidirectional"))
    )
    (net (code "90") (name "unconnected-(JP12-Pad5)") (class "Default")
      (node (ref "JP12") (pin "5") (pinfunction "5_5") (pintype "passive"))
    )
    (net (code "91") (name "unconnected-(U$6-Pad18)") (class "Default")
      (node (ref "U$6") (pin "18") (pinfunction "18_18") (pintype "passive"))
    )
    (net (code "92") (name "unconnected-(U$6-Pad22)") (class "Default")
      (node (ref "U$6") (pin "22") (pinfunction "22_22") (pintype "passive"))
    )
    (net (code "93") (name "unconnected-(U$6-Pad23)") (class "Default")
      (node (ref "U$6") (pin "23") (pinfunction "23_23") (pintype "passive"))
    )
    (net (code "94") (name "unconnected-(U$6-Pad24)") (class "Default")
      (node (ref "U$6") (pin "24") (pinfunction "24_24") (pintype "passive"))
    )
    (net (code "95") (name "unconnected-(U$6-Pad25)") (class "Default")
      (node (ref "U$6") (pin "25") (pinfunction "25_25") (pintype "passive"))
    )
    (net (code "96") (name "unconnected-(U$6-Pad26)") (class "Default")
      (node (ref "U$6") (pin "26") (pinfunction "26_26") (pintype "passive"))
    )
    (net (code "97") (name "unconnected-(U$6-Pad27)") (class "Default")
      (node (ref "U$6") (pin "27") (pinfunction "27_27") (pintype "passive"))
    )
    (net (code "98") (name "unconnected-(U$6-Pad28)") (class "Default")
      (node (ref "U$6") (pin "28") (pinfunction "28_28") (pintype "passive"))
    )
    (net (code "99") (name "unconnected-(U$6-Pad30)") (class "Default")
      (node (ref "U$6") (pin "30") (pinfunction "30_30") (pintype "passive"))
    )
    (net (code "100") (name "unconnected-(U1-NC-Pad1)") (class "Default")
      (node (ref "U1") (pin "1") (pinfunction "NC_1") (pintype "bidirectional"))
    )
    (net (code "101") (name "unconnected-(U1-PadCD1)") (class "Default")
      (node (ref "U1") (pin "CD1") (pinfunction "CD1_CD1") (pintype "bidirectional"))
    )
    (net (code "102") (name "unconnected-(U1-PadCD2)") (class "Default")
      (node (ref "U1") (pin "CD2") (pinfunction "CD2_CD2") (pintype "bidirectional"))
    )
    (net (code "103") (name "unconnected-(U1-RSV-Pad8)") (class "Default")
      (node (ref "U1") (pin "8") (pinfunction "RSV_8") (pintype "bidirectional"))
    )
    (net (code "104") (name "unconnected-(U2-PB7-Pad13)") (class "Default")
      (node (ref "U2") (pin "13") (pinfunction "PB7_13") (pintype "bidirectional"))
    )
    (net (code "105") (name "unconnected-(U2-PD1-Pad27)") (class "Default")
      (node (ref "U2") (pin "27") (pinfunction "PD1_27") (pintype "bidirectional"))
    )
    (net (code "106") (name "unconnected-(U2-PF4-Pad50)") (class "Default")
      (node (ref "U2") (pin "50") (pinfunction "PF4_50") (pintype "bidirectional"))
    )
    (net (code "107") (name "unconnected-(U2-PF5-Pad51)") (class "Default")
      (node (ref "U2") (pin "51") (pinfunction "PF5_51") (pintype "bidirectional"))
    )
    (net (code "108") (name "unconnected-(U2-PF7-Pad55)") (class "Default")
      (node (ref "U2") (pin "55") (pinfunction "PF7_55") (pintype "bidirectional"))
    )
  )
)
